# mainboard.net
KiCad netlist of a schematic drawn in EAGLE
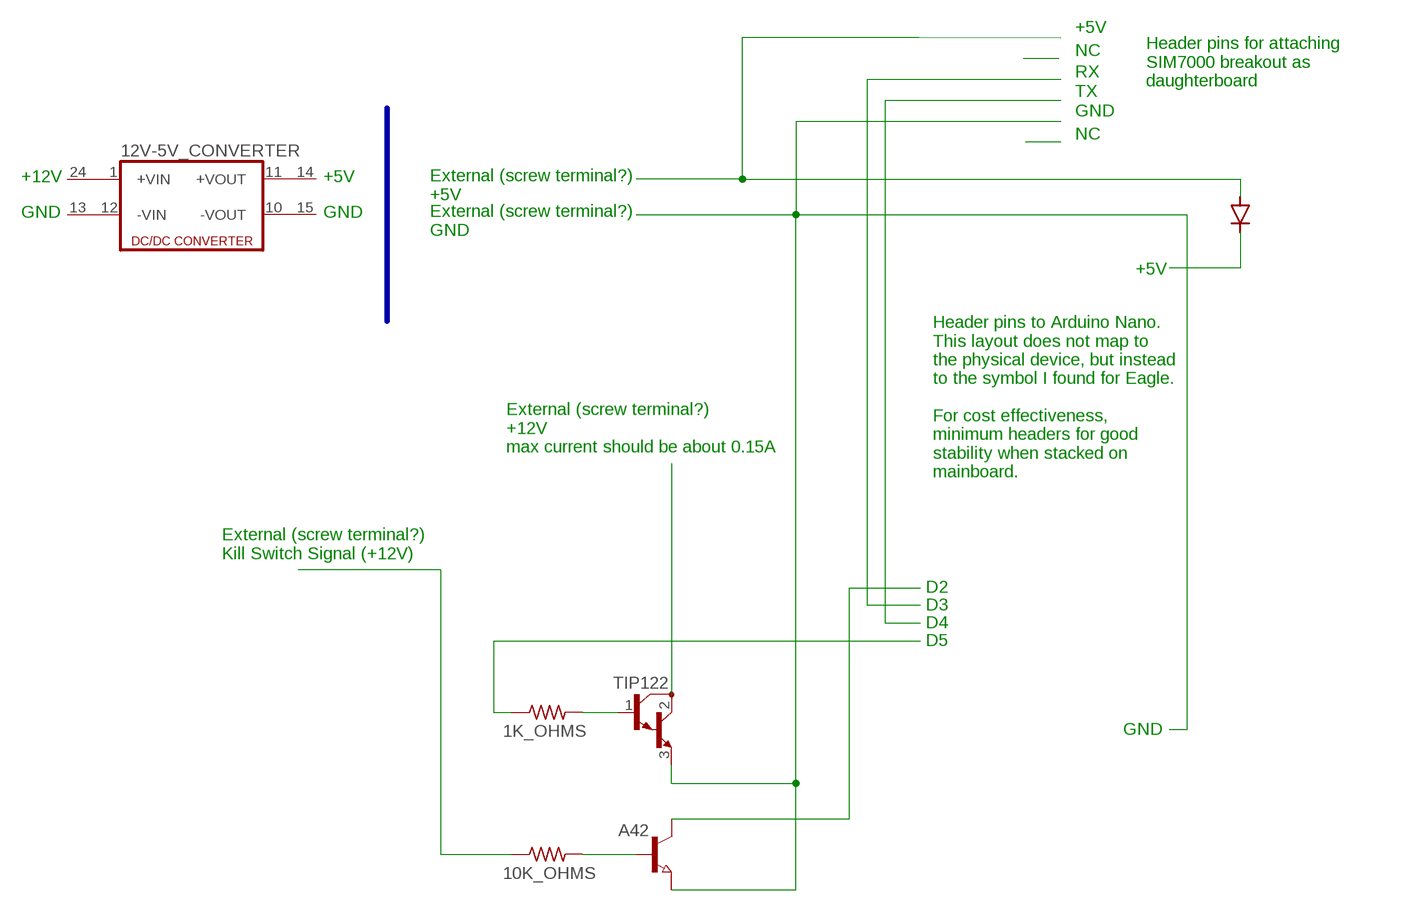
[diagram p0: schematic, sheet 1]

(export (version "E")
  (design (tool "Eeschema 10.0.6"))
  (components
    (comp (ref "1K_OHMS")
      (value "R-US_0411/15")
      (footprint "eagle-import:0411_15")
      (libsource (lib "eagle-import") (part "R-US_0411/15"))
    )
    (comp (ref "10K_OHMS")
      (value "R-US_0411/15")
      (footprint "eagle-import:0411_15")
      (libsource (lib "eagle-import") (part "R-US_0411/15"))
    )
    (comp (ref "12V-5V_CONVERTER")
      (value "DC213R")
      (footprint "eagle-import:CMK")
      (libsource (lib "eagle-import") (part "DC213R"))
    )
    (comp (ref "A42")
      (value "NPN-TRANSISTOR_SOT23")
      (footprint "eagle-import:SOT23")
      (libsource (lib "eagle-import") (part "NPN-TRANSISTOR_SOT23"))
    )
    (comp (ref "D2")
      (value "1N5400")
      (footprint "eagle-import:DO201-15")
      (libsource (lib "eagle-import") (part "1N5400"))
    )
    (comp (ref "Q1")
      (value "TIP122")
      (footprint "eagle-import:TO220")
      (libsource (lib "eagle-import") (part "TIP122"))
    )
  )
  (nets
    (net (code "1") (name "Net-(A42-B)") (class "Default")
      (node (ref "10K_OHMS") (pin "2") (pinfunction "2_2") (pintype "passive"))
      (node (ref "A42") (pin "1") (pinfunction "B_1") (pintype "passive"))
    )
    (net (code "2") (name "Net-(A42-E)") (class "Default")
      (node (ref "A42") (pin "2") (pinfunction "E_2") (pintype "passive"))
      (node (ref "Q1") (pin "3") (pinfunction "E_3") (pintype "passive"))
    )
    (net (code "3") (name "Net-(Q1-B)") (class "Default")
      (node (ref "1K_OHMS") (pin "2") (pinfunction "2_2") (pintype "passive"))
      (node (ref "Q1") (pin "1") (pinfunction "B_1") (pintype "passive"))
    )
    (net (code "4") (name "unconnected-(1K_OHMS-Pad1)") (class "Default")
      (node (ref "1K_OHMS") (pin "1") (pinfunction "1_1") (pintype "passive"))
    )
    (net (code "5") (name "unconnected-(10K_OHMS-Pad1)") (class "Default")
      (node (ref "10K_OHMS") (pin "1") (pinfunction "1_1") (pintype "passive"))
    )
    (net (code "6") (name "unconnected-(12V-5V_CONVERTER-+VIN-Pad1)") (class "Default")
      (node (ref "12V-5V_CONVERTER") (pin "1") (pinfunction "+VIN_1") (pintype "passive"))
    )
    (net (code "7") (name "unconnected-(12V-5V_CONVERTER-+VIN1-Pad24)") (class "Default")
      (node (ref "12V-5V_CONVERTER") (pin "24") (pinfunction "+VIN1_24") (pintype "passive"))
    )
    (net (code "8") (name "unconnected-(12V-5V_CONVERTER-+VOUT-Pad11)") (class "Default")
      (node (ref "12V-5V_CONVERTER") (pin "11") (pinfunction "+VOUT_11") (pintype "passive"))
    )
    (net (code "9") (name "unconnected-(12V-5V_CONVERTER-+VOUT1-Pad14)") (class "Default")
      (node (ref "12V-5V_CONVERTER") (pin "14") (pinfunction "+VOUT1_14") (pintype "passive"))
    )
    (net (code "10") (name "unconnected-(12V-5V_CONVERTER--VIN-Pad12)") (class "Default")
      (node (ref "12V-5V_CONVERTER") (pin "12") (pinfunction "-VIN_12") (pintype "passive"))
    )
    (net (code "11") (name "unconnected-(12V-5V_CONVERTER--VIN1-Pad13)") (class "Default")
      (node (ref "12V-5V_CONVERTER") (pin "13") (pinfunction "-VIN1_13") (pintype "passive"))
    )
    (net (code "12") (name "unconnected-(12V-5V_CONVERTER--VOUT-Pad10)") (class "Default")
      (node (ref "12V-5V_CONVERTER") (pin "10") (pinfunction "-VOUT_10") (pintype "passive"))
    )
    (net (code "13") (name "unconnected-(12V-5V_CONVERTER--VOUT1-Pad15)") (class "Default")
      (node (ref "12V-5V_CONVERTER") (pin "15") (pinfunction "-VOUT1_15") (pintype "passive"))
    )
    (net (code "14") (name "unconnected-(A42-C-Pad3)") (class "Default")
      (node (ref "A42") (pin "3") (pinfunction "C_3") (pintype "passive"))
    )
    (net (code "15") (name "unconnected-(D2-PadA)") (class "Default")
      (node (ref "D2") (pin "A") (pinfunction "A_A") (pintype "passive"))
    )
    (net (code "16") (name "unconnected-(D2-PadC)") (class "Default")
      (node (ref "D2") (pin "C") (pinfunction "C_C") (pintype "passive"))
    )
    (net (code "17") (name "unconnected-(Q1-C-Pad2)") (class "Default")
      (node (ref "Q1") (pin "2") (pinfunction "C_2") (pintype "passive"))
    )
  )
)
